# SH2_-_CONNECTORS.net
KiCad netlist of a schematic drawn in Altium Designer
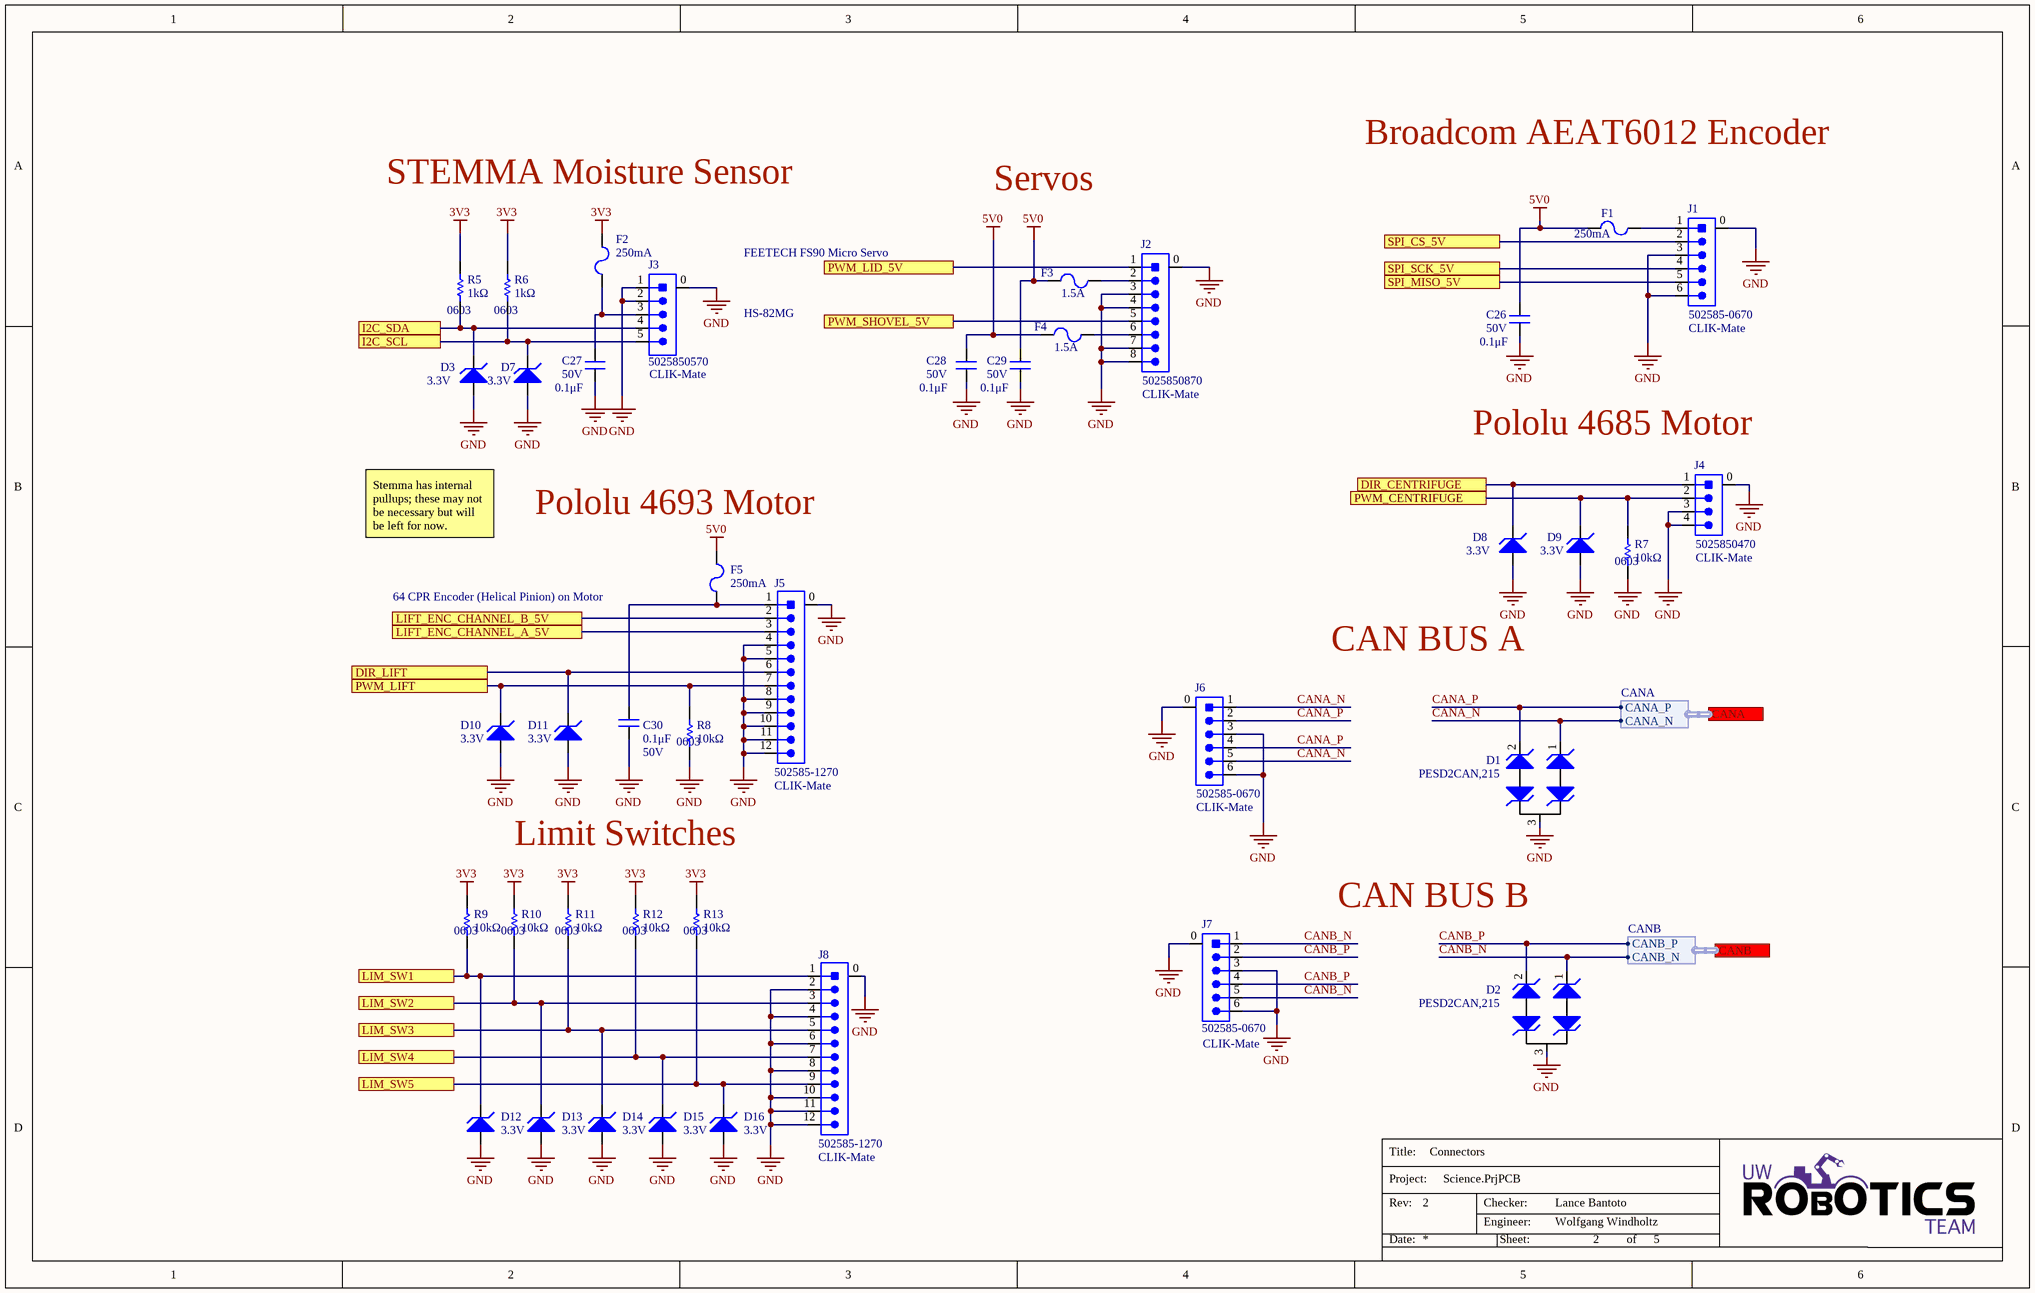
[diagram p0: SH2 - CONNECTORS.SchDoc]

(export (version "E")
  (design (tool "Eeschema 10.0.6"))
  (components
    (comp (ref "C26")
      (value "0.1μF")
      (footprint "CAP0603")
      (description "CAP CER 0.1UF 50V X7R 0603")
      (fields (field (name "VOLTAGE RATING") "50V") (field (name "Comment") "CAP_0.1uF_50V_0603"))
      (libsource (lib "UWRT_Schematic_Library_2020") (part "CAP_0.1uF_50V_0603"))
    )
    (comp (ref "C27")
      (value "0.1μF")
      (footprint "CAP0603")
      (description "CAP CER 0.1UF 50V X7R 0603")
      (fields (field (name "VOLTAGE RATING") "50V") (field (name "Comment") "CAP_0.1uF_50V_0603"))
      (libsource (lib "UWRT_Schematic_Library_2020") (part "CAP_0.1uF_50V_0603"))
    )
    (comp (ref "C28")
      (value "0.1μF")
      (footprint "CAP0603")
      (description "CAP CER 0.1UF 50V X7R 0603")
      (fields (field (name "VOLTAGE RATING") "50V") (field (name "Comment") "CAP_0.1uF_50V_0603"))
      (libsource (lib "UWRT_Schematic_Library_2020") (part "CAP_0.1uF_50V_0603"))
    )
    (comp (ref "C29")
      (value "0.1μF")
      (footprint "CAP0603")
      (description "CAP CER 0.1UF 50V X7R 0603")
      (fields (field (name "VOLTAGE RATING") "50V") (field (name "Comment") "CAP_0.1uF_50V_0603"))
      (libsource (lib "UWRT_Schematic_Library_2020") (part "CAP_0.1uF_50V_0603"))
    )
    (comp (ref "C30")
      (value "0.1μF")
      (footprint "CAP0603")
      (description "CAP CER 0.1UF 50V X7R 0603")
      (fields (field (name "VOLTAGE RATING") "50V") (field (name "Comment") "CAP_0.1uF_50V_0603"))
      (libsource (lib "UWRT_Schematic_Library_2020") (part "CAP_0.1uF_50V_0603"))
    )
    (comp (ref "D1")
      (value "TVS_DIODE_CAN")
      (footprint "TVS_DIODE_CAN")
      (description "TVS DIODE 24V 41V SOT323-3")
      (fields (field (name "MANUFACTURER PART NUMBER 1") "PESD2CAN,215"))
      (libsource (lib "UWRT_Schematic_Library_2020") (part "TVS_DIODE_CAN"))
    )
    (comp (ref "D2")
      (value "TVS_DIODE_CAN")
      (footprint "TVS_DIODE_CAN")
      (description "TVS DIODE 24V 41V SOT323-3")
      (fields (field (name "MANUFACTURER PART NUMBER 1") "PESD2CAN,215"))
      (libsource (lib "UWRT_Schematic_Library_2020") (part "TVS_DIODE_CAN"))
    )
    (comp (ref "D3")
      (value "ESD5Z3.3T1G")
      (footprint "SOD523_UNI")
      (description "TVS DIODE 3.3V 14.1V SOD523")
      (fields (field (name "REVERSE STANDOFF VOLTAGE") "3.3V"))
      (libsource (lib "UWRT_Schematic_Library_2020") (part "ESD5Z3.3T1G"))
    )
    (comp (ref "D7")
      (value "ESD5Z3.3T1G")
      (footprint "SOD523_UNI")
      (description "TVS DIODE 3.3V 14.1V SOD523")
      (fields (field (name "REVERSE STANDOFF VOLTAGE") "3.3V"))
      (libsource (lib "UWRT_Schematic_Library_2020") (part "ESD5Z3.3T1G"))
    )
    (comp (ref "D8")
      (value "ESD5Z3.3T1G")
      (footprint "SOD523_UNI")
      (description "TVS DIODE 3.3V 14.1V SOD523")
      (fields (field (name "REVERSE STANDOFF VOLTAGE") "3.3V"))
      (libsource (lib "UWRT_Schematic_Library_2020") (part "ESD5Z3.3T1G"))
    )
    (comp (ref "D9")
      (value "ESD5Z3.3T1G")
      (footprint "SOD523_UNI")
      (description "TVS DIODE 3.3V 14.1V SOD523")
      (fields (field (name "REVERSE STANDOFF VOLTAGE") "3.3V"))
      (libsource (lib "UWRT_Schematic_Library_2020") (part "ESD5Z3.3T1G"))
    )
    (comp (ref "D10")
      (value "ESD5Z3.3T1G")
      (footprint "SOD523_UNI")
      (description "TVS DIODE 3.3V 14.1V SOD523")
      (fields (field (name "REVERSE STANDOFF VOLTAGE") "3.3V"))
      (libsource (lib "UWRT_Schematic_Library_2020") (part "ESD5Z3.3T1G"))
    )
    (comp (ref "D11")
      (value "ESD5Z3.3T1G")
      (footprint "SOD523_UNI")
      (description "TVS DIODE 3.3V 14.1V SOD523")
      (fields (field (name "REVERSE STANDOFF VOLTAGE") "3.3V"))
      (libsource (lib "UWRT_Schematic_Library_2020") (part "ESD5Z3.3T1G"))
    )
    (comp (ref "D12")
      (value "ESD5Z3.3T1G")
      (footprint "SOD523_UNI")
      (description "TVS DIODE 3.3V 14.1V SOD523")
      (fields (field (name "REVERSE STANDOFF VOLTAGE") "3.3V"))
      (libsource (lib "UWRT_Schematic_Library_2020") (part "ESD5Z3.3T1G"))
    )
    (comp (ref "D13")
      (value "ESD5Z3.3T1G")
      (footprint "SOD523_UNI")
      (description "TVS DIODE 3.3V 14.1V SOD523")
      (fields (field (name "REVERSE STANDOFF VOLTAGE") "3.3V"))
      (libsource (lib "UWRT_Schematic_Library_2020") (part "ESD5Z3.3T1G"))
    )
    (comp (ref "D14")
      (value "ESD5Z3.3T1G")
      (footprint "SOD523_UNI")
      (description "TVS DIODE 3.3V 14.1V SOD523")
      (fields (field (name "REVERSE STANDOFF VOLTAGE") "3.3V"))
      (libsource (lib "UWRT_Schematic_Library_2020") (part "ESD5Z3.3T1G"))
    )
    (comp (ref "D15")
      (value "ESD5Z3.3T1G")
      (footprint "SOD523_UNI")
      (description "TVS DIODE 3.3V 14.1V SOD523")
      (fields (field (name "REVERSE STANDOFF VOLTAGE") "3.3V"))
      (libsource (lib "UWRT_Schematic_Library_2020") (part "ESD5Z3.3T1G"))
    )
    (comp (ref "D16")
      (value "ESD5Z3.3T1G")
      (footprint "SOD523_UNI")
      (description "TVS DIODE 3.3V 14.1V SOD523")
      (fields (field (name "REVERSE STANDOFF VOLTAGE") "3.3V"))
      (libsource (lib "UWRT_Schematic_Library_2020") (part "ESD5Z3.3T1G"))
    )
    (comp (ref "F1")
      (value "FUSE_250mA_1206")
      (footprint "FUSE_1206")
      (description "FUSE BOARD MNT 250MA 125VAC/VDC")
      (fields (field (name "CURRENT RATING") "250mA"))
      (libsource (lib "UWRT_Schematic_Library_2020") (part "FUSE_250mA_1206"))
    )
    (comp (ref "F2")
      (value "FUSE_250mA_1206")
      (footprint "FUSE_1206")
      (description "FUSE BOARD MNT 250MA 125VAC/VDC")
      (fields (field (name "CURRENT RATING") "250mA"))
      (libsource (lib "UWRT_Schematic_Library_2020") (part "FUSE_250mA_1206"))
    )
    (comp (ref "F3")
      (value "FUSE_1.5A_1206")
      (footprint "FUSE_1206")
      (description "FUSE SMD 1.5A 63V")
      (fields (field (name "CURRENT RATING") "1.5A"))
      (libsource (lib "UWRT_Schematic_Library_2020") (part "FUSE_1.5A_1206"))
    )
    (comp (ref "F4")
      (value "FUSE_1.5A_1206")
      (footprint "FUSE_1206")
      (description "FUSE SMD 1.5A 63V")
      (fields (field (name "CURRENT RATING") "1.5A"))
      (libsource (lib "UWRT_Schematic_Library_2020") (part "FUSE_1.5A_1206"))
    )
    (comp (ref "F5")
      (value "FUSE_250mA_1206")
      (footprint "FUSE_1206")
      (description "FUSE BOARD MNT 250MA 125VAC/VDC")
      (fields (field (name "CURRENT RATING") "250mA"))
      (libsource (lib "UWRT_Schematic_Library_2020") (part "FUSE_250mA_1206"))
    )
    (comp (ref "J1")
      (value "CON_6M_SM_RA_1.5mm")
      (footprint "MOLEX-5025850670")
      (description "CONN HEADER SMD RIGHT ANGLE 1.5 MM PITCH")
      (fields
        (field (name "MANUFACTOR NUMBER") "502585-0670")
        (field (name "MANUFACTURER") "Molex")
        (field (name "FAMILY") "CLIK-Mate")
      )
      (libsource (lib "") (part "CON_6M_SM_RA_1.5mm_1"))
    )
    (comp (ref "J2")
      (value "CON_8M_SM_RA")
      (footprint "MOLEX-5025850870")
      (description "CONN HEADER SMD RIGHT ANGLE 1.5 MM PITCH")
      (fields
        (field (name "MANUFACTURER") "Molex")
        (field (name "MANUFACTURER PART NUMBER") "5025850870")
        (field (name "FAMILY") "CLIK-Mate")
      )
      (libsource (lib "UWRT_Schematic_Library_2020") (part "CON_8M_SM_RA"))
    )
    (comp (ref "J3")
      (value "CON_5M_SM_RA")
      (footprint "MOLEX-5025850570")
      (description "CONN HEADER SMD RIGHT ANGLE 1.5MM PITCH")
      (fields (field (name "MANUFACTURER PART NUMBER 1") "5025850570") (field (name "FAMILY") "CLIK-Mate"))
      (libsource (lib "UWRT_Schematic_Library_2020") (part "CON_5M_SM_RA"))
    )
    (comp (ref "J4")
      (value "CON_4M_SM_RA")
      (footprint "MOLEX-5025850470")
      (description "CONN HEADER SMD RIGHT ANGLE 1.5 MM PITCH")
      (fields
        (field (name "MANUFACTOR NUMBER") "5025850470")
        (field (name "MANUFACTURER") "Molex")
        (field (name "FAMILY") "CLIK-Mate")
      )
      (libsource (lib "UWRT_Schematic_Library_2020") (part "CON_4M_SM_RA"))
    )
    (comp (ref "J5")
      (value "CON_12M_SM_RA")
      (footprint "MOLEX-5025851270")
      (description "CONN HEADER SMD RIGHT ANGLE 1.5MM PITCH")
      (fields (field (name "FAMILY") "CLIK-Mate") (field (name "MANUFACTURER PART NUMBER 1") "502585-1270"))
      (libsource (lib "UWRT_Schematic_Library_2020") (part "CON_12M_SM_RA"))
    )
    (comp (ref "J6")
      (value "CON_6M_SM_RA_1.5mm")
      (footprint "MOLEX-5025850670")
      (description "CONN HEADER SMD RIGHT ANGLE 1.5 MM PITCH")
      (fields
        (field (name "MANUFACTOR NUMBER") "502585-0670")
        (field (name "MANUFACTURER") "Molex")
        (field (name "FAMILY") "CLIK-Mate")
      )
      (libsource (lib "UWRT_Schematic_Library_2020") (part "CON_6M_SM_RA_1.5mm"))
    )
    (comp (ref "J7")
      (value "CON_6M_SM_RA_1.5mm")
      (footprint "MOLEX-5025850670")
      (description "CONN HEADER SMD RIGHT ANGLE 1.5 MM PITCH")
      (fields
        (field (name "MANUFACTOR NUMBER") "502585-0670")
        (field (name "MANUFACTURER") "Molex")
        (field (name "FAMILY") "CLIK-Mate")
      )
      (libsource (lib "UWRT_Schematic_Library_2020") (part "CON_6M_SM_RA_1.5mm"))
    )
    (comp (ref "J8")
      (value "CON_12M_SM_RA")
      (footprint "MOLEX-5025851270")
      (description "CONN HEADER SMD RIGHT ANGLE 1.5MM PITCH")
      (fields (field (name "FAMILY") "CLIK-Mate") (field (name "MANUFACTURER PART NUMBER 1") "502585-1270"))
      (libsource (lib "UWRT_Schematic_Library_2020") (part "CON_12M_SM_RA"))
    )
    (comp (ref "R5")
      (value "1kΩ")
      (footprint "RESC0603")
      (description "RES 1K OHM 5% 1/10W 0603")
      (fields
        (field (name "TOLERANCE") "5%")
        (field (name "PACKAGE/FOOTPRINT") "0603")
        (field (name "Comment") "RES_1kΩ_0603_5%")
      )
      (libsource (lib "UWRT_Schematic_Library_2020") (part "RES_1kΩ_0603_5%"))
    )
    (comp (ref "R6")
      (value "1kΩ")
      (footprint "RESC0603")
      (description "RES 1K OHM 5% 1/10W 0603")
      (fields
        (field (name "TOLERANCE") "5%")
        (field (name "PACKAGE/FOOTPRINT") "0603")
        (field (name "Comment") "RES_1kΩ_0603_5%")
      )
      (libsource (lib "UWRT_Schematic_Library_2020") (part "RES_1kΩ_0603_5%"))
    )
    (comp (ref "R7")
      (value "10kΩ")
      (footprint "RESC0603")
      (description "RES 10K OHM 5% 1/10W 0603")
      (fields
        (field (name "TOLERANCE") "5%")
        (field (name "PACKAGE/FOOTPRINT") "0603")
        (field (name "Comment") "RES_10kΩ_0603_5%")
      )
      (libsource (lib "UWRT_Schematic_Library_2020") (part "RES_10kΩ_0603_5%"))
    )
    (comp (ref "R8")
      (value "10kΩ")
      (footprint "RESC0603")
      (description "RES 10K OHM 5% 1/10W 0603")
      (fields
        (field (name "TOLERANCE") "5%")
        (field (name "PACKAGE/FOOTPRINT") "0603")
        (field (name "Comment") "RES_10kΩ_0603_5%")
      )
      (libsource (lib "UWRT_Schematic_Library_2020") (part "RES_10kΩ_0603_5%"))
    )
    (comp (ref "R9")
      (value "10kΩ")
      (footprint "RESC0603")
      (description "RES 10K OHM 5% 1/10W 0603")
      (fields
        (field (name "TOLERANCE") "5%")
        (field (name "PACKAGE/FOOTPRINT") "0603")
        (field (name "Comment") "RES_10kΩ_0603_5%")
      )
      (libsource (lib "UWRT_Schematic_Library_2020") (part "RES_10kΩ_0603_5%"))
    )
    (comp (ref "R10")
      (value "10kΩ")
      (footprint "RESC0603")
      (description "RES 10K OHM 5% 1/10W 0603")
      (fields
        (field (name "TOLERANCE") "5%")
        (field (name "PACKAGE/FOOTPRINT") "0603")
        (field (name "Comment") "RES_10kΩ_0603_5%")
      )
      (libsource (lib "UWRT_Schematic_Library_2020") (part "RES_10kΩ_0603_5%"))
    )
    (comp (ref "R11")
      (value "10kΩ")
      (footprint "RESC0603")
      (description "RES 10K OHM 5% 1/10W 0603")
      (fields
        (field (name "TOLERANCE") "5%")
        (field (name "PACKAGE/FOOTPRINT") "0603")
        (field (name "Comment") "RES_10kΩ_0603_5%")
      )
      (libsource (lib "UWRT_Schematic_Library_2020") (part "RES_10kΩ_0603_5%"))
    )
    (comp (ref "R12")
      (value "10kΩ")
      (footprint "RESC0603")
      (description "RES 10K OHM 5% 1/10W 0603")
      (fields
        (field (name "TOLERANCE") "5%")
        (field (name "PACKAGE/FOOTPRINT") "0603")
        (field (name "Comment") "RES_10kΩ_0603_5%")
      )
      (libsource (lib "UWRT_Schematic_Library_2020") (part "RES_10kΩ_0603_5%"))
    )
    (comp (ref "R13")
      (value "10kΩ")
      (footprint "RESC0603")
      (description "RES 10K OHM 5% 1/10W 0603")
      (fields
        (field (name "TOLERANCE") "5%")
        (field (name "PACKAGE/FOOTPRINT") "0603")
        (field (name "Comment") "RES_10kΩ_0603_5%")
      )
      (libsource (lib "UWRT_Schematic_Library_2020") (part "RES_10kΩ_0603_5%"))
    )
  )
  (nets
    (net (code "3") (name "/CANA_N") (class "Default")
      (node (ref "D1") (pin "1") (pinfunction "1_1") (pintype "passive"))
      (node (ref "J6") (pin "1") (pinfunction "1_1") (pintype "passive"))
      (node (ref "J6") (pin "5") (pinfunction "5_5") (pintype "passive"))
    )
    (net (code "4") (name "/CANA_P") (class "Default")
      (node (ref "D1") (pin "2") (pinfunction "2_2") (pintype "passive"))
      (node (ref "J6") (pin "2") (pinfunction "2_2") (pintype "passive"))
      (node (ref "J6") (pin "4") (pinfunction "4_4") (pintype "passive"))
    )
    (net (code "5") (name "/CANB_N") (class "Default")
      (node (ref "D2") (pin "1") (pinfunction "1_1") (pintype "passive"))
      (node (ref "J7") (pin "1") (pinfunction "1_1") (pintype "passive"))
      (node (ref "J7") (pin "5") (pinfunction "5_5") (pintype "passive"))
    )
    (net (code "6") (name "/CANB_P") (class "Default")
      (node (ref "D2") (pin "2") (pinfunction "2_2") (pintype "passive"))
      (node (ref "J7") (pin "2") (pinfunction "2_2") (pintype "passive"))
      (node (ref "J7") (pin "4") (pinfunction "4_4") (pintype "passive"))
    )
    (net (code "7") (name "/DIR_CENTRIFUGE") (class "Default")
      (node (ref "D8") (pin "2") (pinfunction "Cathode_2") (pintype "passive"))
      (node (ref "J4") (pin "1") (pinfunction "1_1") (pintype "passive"))
    )
    (net (code "8") (name "/DIR_LIFT") (class "Default")
      (node (ref "D11") (pin "2") (pinfunction "Cathode_2") (pintype "passive"))
      (node (ref "J5") (pin "6") (pinfunction "6_6") (pintype "passive"))
    )
    (net (code "9") (name "/I2C_SCL") (class "Default")
      (node (ref "D7") (pin "2") (pinfunction "Cathode_2") (pintype "passive"))
      (node (ref "J3") (pin "5") (pinfunction "5_5") (pintype "passive"))
      (node (ref "R6") (pin "1") (pinfunction "1_1") (pintype "passive"))
    )
    (net (code "10") (name "/I2C_SDA") (class "Default")
      (node (ref "D3") (pin "2") (pinfunction "Cathode_2") (pintype "passive"))
      (node (ref "J3") (pin "4") (pinfunction "4_4") (pintype "passive"))
      (node (ref "R5") (pin "1") (pinfunction "1_1") (pintype "passive"))
    )
    (net (code "11") (name "/LIFT_ENC_CHANNEL_A_5V") (class "Default")
      (node (ref "J5") (pin "3") (pinfunction "3_3") (pintype "passive"))
    )
    (net (code "12") (name "/LIFT_ENC_CHANNEL_B_5V") (class "Default")
      (node (ref "J5") (pin "2") (pinfunction "2_2") (pintype "passive"))
    )
    (net (code "13") (name "/LIM_SW1") (class "Default")
      (node (ref "D12") (pin "2") (pinfunction "Cathode_2") (pintype "passive"))
      (node (ref "J8") (pin "1") (pinfunction "1_1") (pintype "passive"))
      (node (ref "R9") (pin "1") (pinfunction "1_1") (pintype "passive"))
    )
    (net (code "14") (name "/LIM_SW2") (class "Default")
      (node (ref "D13") (pin "2") (pinfunction "Cathode_2") (pintype "passive"))
      (node (ref "J8") (pin "3") (pinfunction "3_3") (pintype "passive"))
      (node (ref "R10") (pin "1") (pinfunction "1_1") (pintype "passive"))
    )
    (net (code "15") (name "/LIM_SW3") (class "Default")
      (node (ref "D14") (pin "2") (pinfunction "Cathode_2") (pintype "passive"))
      (node (ref "J8") (pin "5") (pinfunction "5_5") (pintype "passive"))
      (node (ref "R11") (pin "1") (pinfunction "1_1") (pintype "passive"))
    )
    (net (code "16") (name "/LIM_SW4") (class "Default")
      (node (ref "D15") (pin "2") (pinfunction "Cathode_2") (pintype "passive"))
      (node (ref "J8") (pin "7") (pinfunction "6_7") (pintype "passive"))
      (node (ref "R12") (pin "1") (pinfunction "1_1") (pintype "passive"))
    )
    (net (code "17") (name "/LIM_SW5") (class "Default")
      (node (ref "D16") (pin "2") (pinfunction "Cathode_2") (pintype "passive"))
      (node (ref "J8") (pin "9") (pinfunction "9_9") (pintype "passive"))
      (node (ref "R13") (pin "1") (pinfunction "1_1") (pintype "passive"))
    )
    (net (code "18") (name "/PWM_CENTRIFUGE") (class "Default")
      (node (ref "D9") (pin "2") (pinfunction "Cathode_2") (pintype "passive"))
      (node (ref "J4") (pin "2") (pinfunction "2_2") (pintype "passive"))
      (node (ref "R7") (pin "2") (pinfunction "2_2") (pintype "passive"))
    )
    (net (code "19") (name "/PWM_LID_5V") (class "Default")
      (node (ref "J2") (pin "1") (pinfunction "1_1") (pintype "passive"))
    )
    (net (code "20") (name "/PWM_LIFT") (class "Default")
      (node (ref "D10") (pin "2") (pinfunction "Cathode_2") (pintype "passive"))
      (node (ref "J5") (pin "7") (pinfunction "6_7") (pintype "passive"))
      (node (ref "R8") (pin "2") (pinfunction "2_2") (pintype "passive"))
    )
    (net (code "21") (name "/PWM_SHOVEL_5V") (class "Default")
      (node (ref "J2") (pin "5") (pinfunction "5_5") (pintype "passive"))
    )
    (net (code "22") (name "/SPI_CS_5V") (class "Default")
      (node (ref "J1") (pin "2") (pinfunction "2_2") (pintype "passive"))
    )
    (net (code "23") (name "/SPI_MISO_5V") (class "Default")
      (node (ref "J1") (pin "5") (pinfunction "5_5") (pintype "passive"))
    )
    (net (code "24") (name "/SPI_SCK_5V") (class "Default")
      (node (ref "J1") (pin "4") (pinfunction "4_4") (pintype "passive"))
    )
    (net (code "27") (name "3V3") (class "Default")
      (node (ref "F2") (pin "2") (pinfunction "2_2") (pintype "passive"))
      (node (ref "R10") (pin "2") (pinfunction "2_2") (pintype "passive"))
      (node (ref "R11") (pin "2") (pinfunction "2_2") (pintype "passive"))
      (node (ref "R12") (pin "2") (pinfunction "2_2") (pintype "passive"))
      (node (ref "R13") (pin "2") (pinfunction "2_2") (pintype "passive"))
      (node (ref "R5") (pin "2") (pinfunction "2_2") (pintype "passive"))
      (node (ref "R6") (pin "2") (pinfunction "2_2") (pintype "passive"))
      (node (ref "R9") (pin "2") (pinfunction "2_2") (pintype "passive"))
    )
    (net (code "28") (name "5V0") (class "Default")
      (node (ref "C26") (pin "2") (pinfunction "2_2") (pintype "passive"))
      (node (ref "C28") (pin "2") (pinfunction "2_2") (pintype "passive"))
      (node (ref "C29") (pin "2") (pinfunction "2_2") (pintype "passive"))
      (node (ref "F1") (pin "2") (pinfunction "2_2") (pintype "passive"))
      (node (ref "F3") (pin "1") (pinfunction "1_1") (pintype "passive"))
      (node (ref "F4") (pin "1") (pinfunction "1_1") (pintype "passive"))
      (node (ref "F5") (pin "2") (pinfunction "2_2") (pintype "passive"))
    )
    (net (code "29") (name "GND") (class "Default")
      (node (ref "C26") (pin "1") (pinfunction "1_1") (pintype "passive"))
      (node (ref "C27") (pin "1") (pinfunction "1_1") (pintype "passive"))
      (node (ref "C28") (pin "1") (pinfunction "1_1") (pintype "passive"))
      (node (ref "C29") (pin "1") (pinfunction "1_1") (pintype "passive"))
      (node (ref "C30") (pin "1") (pinfunction "1_1") (pintype "passive"))
      (node (ref "D1") (pin "3") (pinfunction "3_3") (pintype "passive"))
      (node (ref "D10") (pin "1") (pinfunction "Anode_1") (pintype "passive"))
      (node (ref "D11") (pin "1") (pinfunction "Anode_1") (pintype "passive"))
      (node (ref "D12") (pin "1") (pinfunction "Anode_1") (pintype "passive"))
      (node (ref "D13") (pin "1") (pinfunction "Anode_1") (pintype "passive"))
      (node (ref "D14") (pin "1") (pinfunction "Anode_1") (pintype "passive"))
      (node (ref "D15") (pin "1") (pinfunction "Anode_1") (pintype "passive"))
      (node (ref "D16") (pin "1") (pinfunction "Anode_1") (pintype "passive"))
      (node (ref "D2") (pin "3") (pinfunction "3_3") (pintype "passive"))
      (node (ref "D3") (pin "1") (pinfunction "Anode_1") (pintype "passive"))
      (node (ref "D7") (pin "1") (pinfunction "Anode_1") (pintype "passive"))
      (node (ref "D8") (pin "1") (pinfunction "Anode_1") (pintype "passive"))
      (node (ref "D9") (pin "1") (pinfunction "Anode_1") (pintype "passive"))
      (node (ref "J1") (pin "0") (pinfunction "0_0") (pintype "passive"))
      (node (ref "J1") (pin "3") (pinfunction "3_3") (pintype "passive"))
      (node (ref "J1") (pin "6") (pinfunction "6_6") (pintype "passive"))
      (node (ref "J2") (pin "0") (pinfunction "0_0") (pintype "passive"))
      (node (ref "J2") (pin "3") (pinfunction "3_3") (pintype "passive"))
      (node (ref "J2") (pin "4") (pinfunction "4_4") (pintype "passive"))
      (node (ref "J2") (pin "7") (pinfunction "6_7") (pintype "passive"))
      (node (ref "J2") (pin "8") (pinfunction "6_8") (pintype "passive"))
      (node (ref "J3") (pin "0") (pinfunction "0_0") (pintype "passive"))
      (node (ref "J3") (pin "1") (pinfunction "1_1") (pintype "passive"))
      (node (ref "J3") (pin "2") (pinfunction "2_2") (pintype "passive"))
      (node (ref "J4") (pin "0") (pinfunction "0_0") (pintype "passive"))
      (node (ref "J4") (pin "3") (pinfunction "3_3") (pintype "passive"))
      (node (ref "J4") (pin "4") (pinfunction "4_4") (pintype "passive"))
      (node (ref "J5") (pin "0") (pinfunction "0_0") (pintype "passive"))
      (node (ref "J5") (pin "10") (pinfunction "10_10") (pintype "passive"))
      (node (ref "J5") (pin "11") (pinfunction "11_11") (pintype "passive"))
      (node (ref "J5") (pin "12") (pinfunction "12_12") (pintype "passive"))
      (node (ref "J5") (pin "4") (pinfunction "4_4") (pintype "passive"))
      (node (ref "J5") (pin "5") (pinfunction "5_5") (pintype "passive"))
      (node (ref "J5") (pin "8") (pinfunction "6_8") (pintype "passive"))
      (node (ref "J5") (pin "9") (pinfunction "9_9") (pintype "passive"))
      (node (ref "J6") (pin "0") (pinfunction "0_0") (pintype "passive"))
      (node (ref "J6") (pin "3") (pinfunction "3_3") (pintype "passive"))
      (node (ref "J6") (pin "6") (pinfunction "6_6") (pintype "passive"))
      (node (ref "J7") (pin "0") (pinfunction "0_0") (pintype "passive"))
      (node (ref "J7") (pin "3") (pinfunction "3_3") (pintype "passive"))
      (node (ref "J7") (pin "6") (pinfunction "6_6") (pintype "passive"))
      (node (ref "J8") (pin "0") (pinfunction "0_0") (pintype "passive"))
      (node (ref "J8") (pin "10") (pinfunction "10_10") (pintype "passive"))
      (node (ref "J8") (pin "11") (pinfunction "11_11") (pintype "passive"))
      (node (ref "J8") (pin "12") (pinfunction "12_12") (pintype "passive"))
      (node (ref "J8") (pin "2") (pinfunction "2_2") (pintype "passive"))
      (node (ref "J8") (pin "4") (pinfunction "4_4") (pintype "passive"))
      (node (ref "J8") (pin "6") (pinfunction "6_6") (pintype "passive"))
      (node (ref "J8") (pin "8") (pinfunction "6_8") (pintype "passive"))
      (node (ref "R7") (pin "1") (pinfunction "1_1") (pintype "passive"))
      (node (ref "R8") (pin "1") (pinfunction "1_1") (pintype "passive"))
    )
    (net (code "30") (name "Net-(C27-Pad2)") (class "Default")
      (node (ref "C27") (pin "2") (pinfunction "2_2") (pintype "passive"))
      (node (ref "F2") (pin "1") (pinfunction "1_1") (pintype "passive"))
      (node (ref "J3") (pin "3") (pinfunction "3_3") (pintype "passive"))
    )
    (net (code "31") (name "Net-(C30-Pad2)") (class "Default")
      (node (ref "C30") (pin "2") (pinfunction "2_2") (pintype "passive"))
      (node (ref "F5") (pin "1") (pinfunction "1_1") (pintype "passive"))
      (node (ref "J5") (pin "1") (pinfunction "1_1") (pintype "passive"))
    )
    (net (code "32") (name "Net-(F1-Pad1)") (class "Default")
      (node (ref "F1") (pin "1") (pinfunction "1_1") (pintype "passive"))
      (node (ref "J1") (pin "1") (pinfunction "1_1") (pintype "passive"))
    )
    (net (code "33") (name "Net-(F3-Pad2)") (class "Default")
      (node (ref "F3") (pin "2") (pinfunction "2_2") (pintype "passive"))
      (node (ref "J2") (pin "2") (pinfunction "2_2") (pintype "passive"))
    )
    (net (code "34") (name "Net-(F4-Pad2)") (class "Default")
      (node (ref "F4") (pin "2") (pinfunction "2_2") (pintype "passive"))
      (node (ref "J2") (pin "6") (pinfunction "6_6") (pintype "passive"))
    )
  )
)
